# lednode2.net
KiCad netlist of a schematic drawn in EAGLE
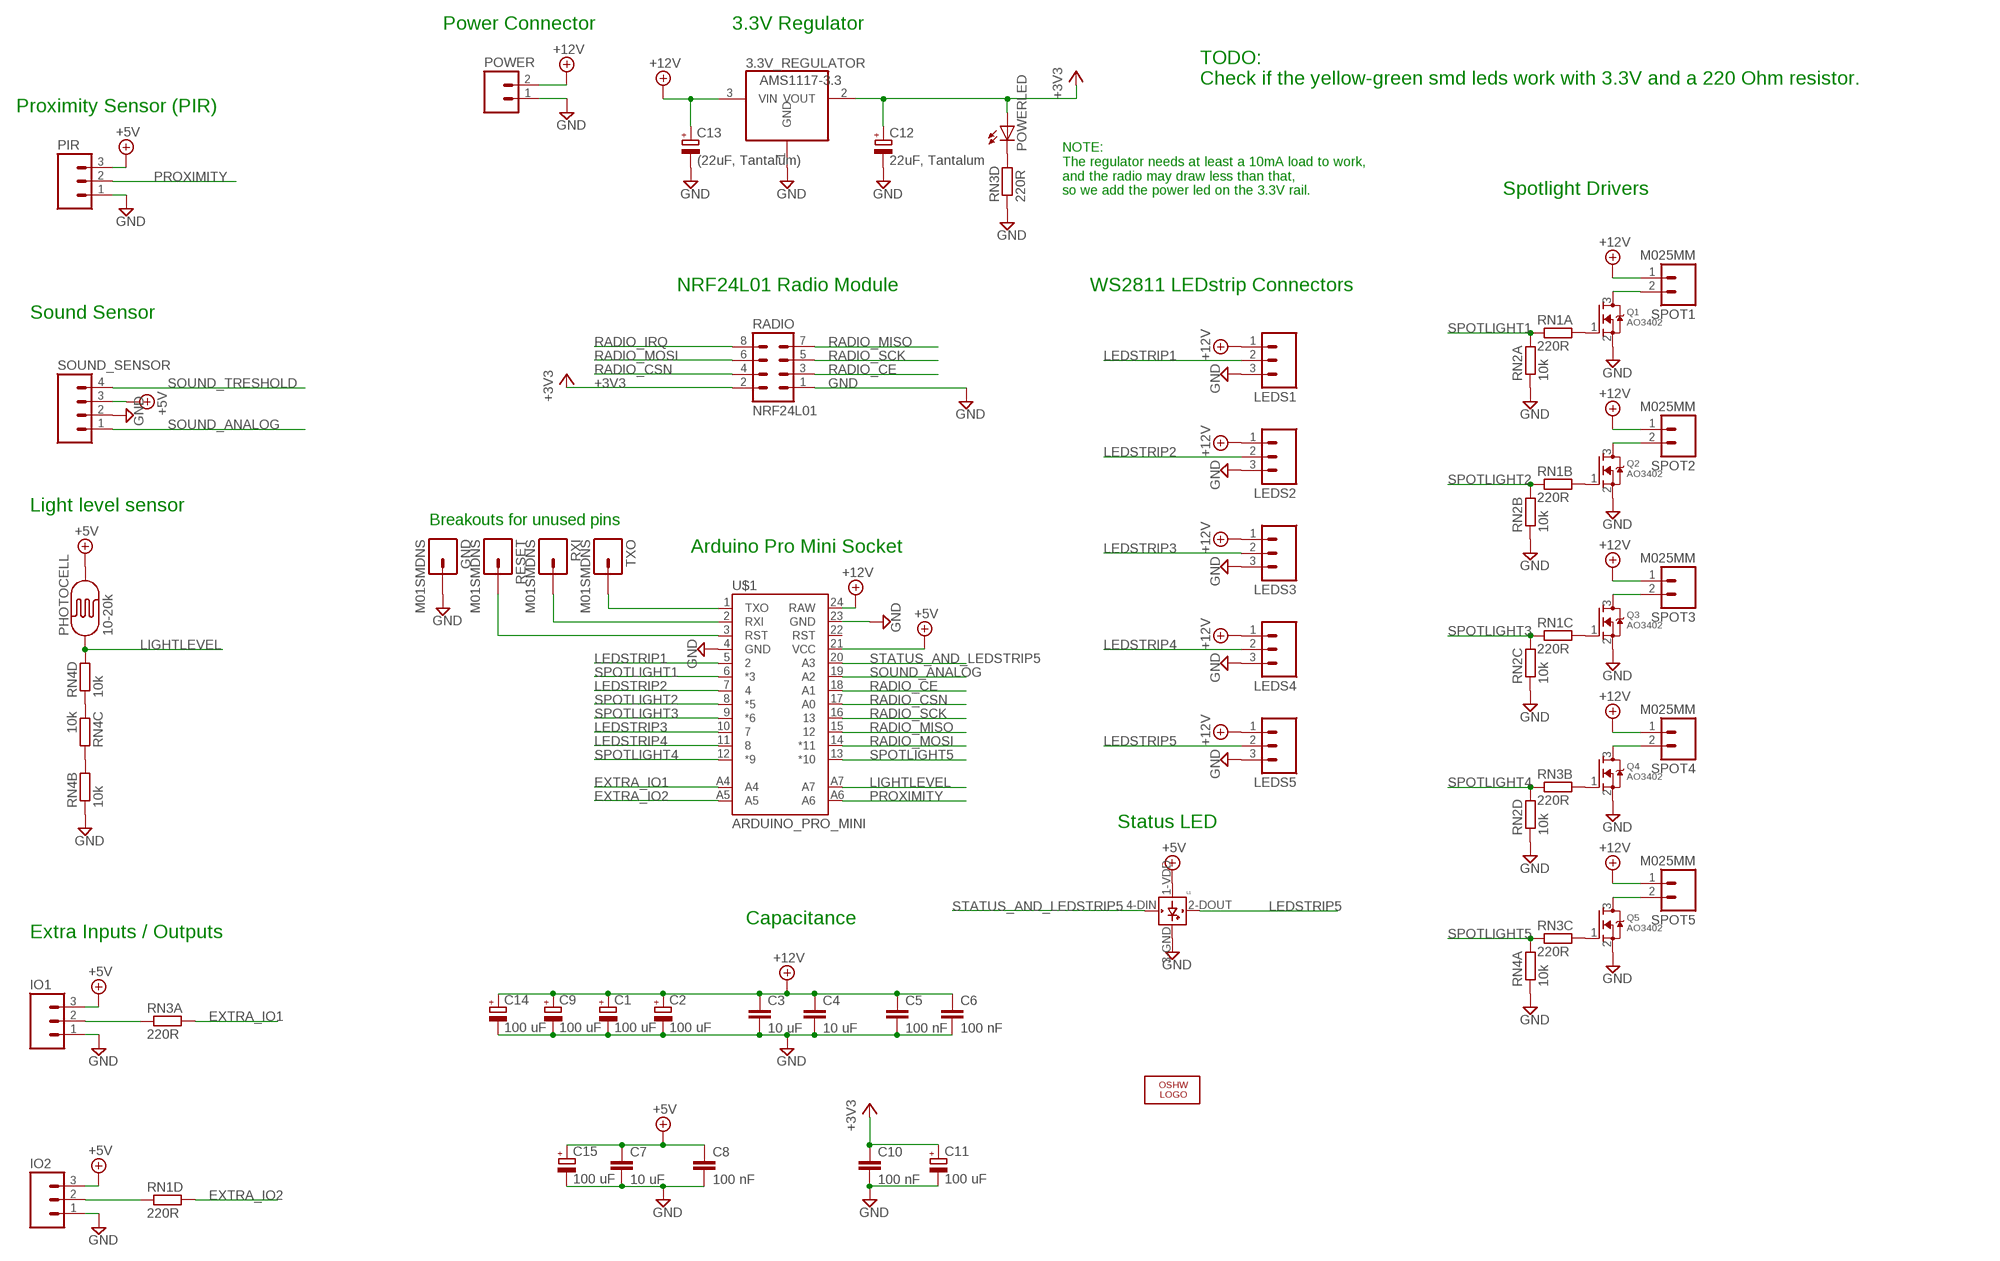
[diagram p0: schematic, sheet 1]

(export (version "E")
  (design (tool "Eeschema 10.0.6"))
  (components
    (comp (ref "3.3V_REGULATOR")
      (value "AMS1117-3.3")
      (footprint "eagle-import:SOT223")
      (fields (field (name "MPN") "REG1117"))
      (libsource (lib "eagle-import") (part "REG1117"))
    )
    (comp (ref "C1")
      (value "100 uF")
      (footprint "eagle-import:E2,5-6")
      (libsource (lib "eagle-import") (part "CPOL-EUE2.5-6"))
    )
    (comp (ref "C2")
      (value "100 uF")
      (footprint "eagle-import:E2,5-6")
      (libsource (lib "eagle-import") (part "CPOL-EUE2.5-6"))
    )
    (comp (ref "C3")
      (value "10 uF")
      (footprint "eagle-import:C1206")
      (libsource (lib "eagle-import") (part "C-EUC1206"))
    )
    (comp (ref "C4")
      (value "10 uF")
      (footprint "eagle-import:C1206")
      (libsource (lib "eagle-import") (part "C-EUC1206"))
    )
    (comp (ref "C5")
      (value "100 nF")
      (footprint "eagle-import:C0805")
      (libsource (lib "eagle-import") (part "C-EUC0805"))
    )
    (comp (ref "C6")
      (value "100 nF")
      (footprint "eagle-import:C0805")
      (libsource (lib "eagle-import") (part "C-EUC0805"))
    )
    (comp (ref "C7")
      (value "10 uF")
      (footprint "eagle-import:C1206")
      (libsource (lib "eagle-import") (part "C-EUC1206"))
    )
    (comp (ref "C8")
      (value "100 nF")
      (footprint "eagle-import:C0805")
      (libsource (lib "eagle-import") (part "C-EUC0805"))
    )
    (comp (ref "C9")
      (value "100 uF")
      (footprint "eagle-import:E2,5-6")
      (libsource (lib "eagle-import") (part "CPOL-EUE2.5-6"))
    )
    (comp (ref "C10")
      (value "100 nF")
      (footprint "eagle-import:C0805")
      (libsource (lib "eagle-import") (part "C-EUC0805"))
    )
    (comp (ref "C11")
      (value "100 uF")
      (footprint "eagle-import:E2,5-6")
      (libsource (lib "eagle-import") (part "CPOL-EUE2.5-6"))
    )
    (comp (ref "C12")
      (value "22uF, Tantalum")
      (footprint "eagle-import:SMC_A")
      (libsource (lib "eagle-import") (part "CPOL-EUSMCA"))
    )
    (comp (ref "C13")
      (value "(22uF, Tantalum)")
      (footprint "eagle-import:SMC_A")
      (libsource (lib "eagle-import") (part "CPOL-EUSMCA"))
    )
    (comp (ref "C14")
      (value "100 uF")
      (footprint "eagle-import:E2,5-6")
      (libsource (lib "eagle-import") (part "CPOL-EUE2.5-6"))
    )
    (comp (ref "C15")
      (value "100 uF")
      (footprint "eagle-import:E2,5-6")
      (libsource (lib "eagle-import") (part "CPOL-EUE2.5-6"))
    )
    (comp (ref "GND")
      (value "M01SMDNS")
      (footprint "eagle-import:1X01NS")
      (libsource (lib "eagle-import") (part "M01SMDNS"))
    )
    (comp (ref "IO1")
      (value "M03PTH")
      (footprint "eagle-import:1X03")
      (libsource (lib "eagle-import") (part "M03PTH"))
    )
    (comp (ref "IO2")
      (value "M03PTH")
      (footprint "eagle-import:1X03")
      (libsource (lib "eagle-import") (part "M03PTH"))
    )
    (comp (ref "L1")
      (value "WS2812B")
      (footprint "eagle-import:WS2812B")
      (libsource (lib "eagle-import") (part "WS2812B"))
    )
    (comp (ref "LEDS1")
      (value "M03LONGPADS")
      (footprint "eagle-import:1X03_LONGPADS")
      (libsource (lib "eagle-import") (part "M03LONGPADS"))
    )
    (comp (ref "LEDS2")
      (value "M03LONGPADS")
      (footprint "eagle-import:1X03_LONGPADS")
      (libsource (lib "eagle-import") (part "M03LONGPADS"))
    )
    (comp (ref "LEDS3")
      (value "M03LONGPADS")
      (footprint "eagle-import:1X03_LONGPADS")
      (libsource (lib "eagle-import") (part "M03LONGPADS"))
    )
    (comp (ref "LEDS4")
      (value "M03LONGPADS")
      (footprint "eagle-import:1X03_LONGPADS")
      (libsource (lib "eagle-import") (part "M03LONGPADS"))
    )
    (comp (ref "LEDS5")
      (value "M03LONGPADS")
      (footprint "eagle-import:1X03_LONGPADS")
      (libsource (lib "eagle-import") (part "M03LONGPADS"))
    )
    (comp (ref "LOGO3")
      (value "LOGO-OSHW-8MILX0100-NT")
      (footprint "eagle-import:OSHW_8X100_NOTEXT")
      (libsource (lib "eagle-import") (part "LOGO-OSHW-8MILX0100-NT"))
    )
    (comp (ref "PHOTOCELL")
      (value "10-20k")
      (footprint "eagle-import:PHOTOCELL")
      (libsource (lib "eagle-import") (part "PHOTOCELLPTH"))
    )
    (comp (ref "PIR")
      (value "M03PTH")
      (footprint "eagle-import:1X03")
      (libsource (lib "eagle-import") (part "M03PTH"))
    )
    (comp (ref "POWER")
      (value "M025MM")
      (footprint "eagle-import:SCREWTERMINAL-5MM-2")
      (libsource (lib "eagle-import") (part "M025MM"))
    )
    (comp (ref "POWERLED")
      (value "LEDSMT1206")
      (footprint "eagle-import:1206")
      (libsource (lib "eagle-import") (part "LEDSMT1206"))
    )
    (comp (ref "Q1")
      (value "AO3402")
      (footprint "eagle-import:SOT23-W")
      (libsource (lib "eagle-import") (part "MOSFET-NWAVE"))
    )
    (comp (ref "Q2")
      (value "AO3402")
      (footprint "eagle-import:SOT23-W")
      (libsource (lib "eagle-import") (part "MOSFET-NWAVE"))
    )
    (comp (ref "Q3")
      (value "AO3402")
      (footprint "eagle-import:SOT23-W")
      (libsource (lib "eagle-import") (part "MOSFET-NWAVE"))
    )
    (comp (ref "Q4")
      (value "AO3402")
      (footprint "eagle-import:SOT23-W")
      (libsource (lib "eagle-import") (part "MOSFET-NWAVE"))
    )
    (comp (ref "Q5")
      (value "AO3402")
      (footprint "eagle-import:SOT23-W")
      (libsource (lib "eagle-import") (part "MOSFET-NWAVE"))
    )
    (comp (ref "RADIO")
      (value "NRF24L01")
      (footprint "eagle-import:MA04-2")
      (libsource (lib "eagle-import") (part "MA04-2"))
    )
    (comp (ref "RESET")
      (value "M01SMDNS")
      (footprint "eagle-import:1X01NS")
      (libsource (lib "eagle-import") (part "M01SMDNS"))
    )
    (comp (ref "RN1")
      (value "220R")
      (footprint "eagle-import:RN8P-4R-CRA06S")
      (libsource (lib "eagle-import") (part "RESISTOR_ARRAY_4"))
    )
    (comp (ref "RN2")
      (value "10k")
      (footprint "eagle-import:RN8P-4R-CRA06S")
      (libsource (lib "eagle-import") (part "RESISTOR_ARRAY_4"))
    )
    (comp (ref "RN3")
      (value "220R")
      (footprint "eagle-import:RN8P-4R-CRA06S")
      (libsource (lib "eagle-import") (part "RESISTOR_ARRAY_4"))
    )
    (comp (ref "RN4")
      (value "10k")
      (footprint "eagle-import:RN8P-4R-CRA06S")
      (libsource (lib "eagle-import") (part "RESISTOR_ARRAY_4"))
    )
    (comp (ref "RXI")
      (value "M01SMDNS")
      (footprint "eagle-import:1X01NS")
      (libsource (lib "eagle-import") (part "M01SMDNS"))
    )
    (comp (ref "SOUND_SENSOR")
      (value "M041X04_NO_SILK")
      (footprint "eagle-import:1X04_NO_SILK")
      (libsource (lib "eagle-import") (part "M041X04_NO_SILK"))
    )
    (comp (ref "SPOT1")
      (value "M025MM")
      (footprint "eagle-import:SCREWTERMINAL-5MM-2")
      (libsource (lib "eagle-import") (part "SparkFun-Connectors_M025MM"))
    )
    (comp (ref "SPOT2")
      (value "M025MM")
      (footprint "eagle-import:SCREWTERMINAL-5MM-2")
      (libsource (lib "eagle-import") (part "SparkFun-Connectors_M025MM"))
    )
    (comp (ref "SPOT3")
      (value "M025MM")
      (footprint "eagle-import:SCREWTERMINAL-5MM-2")
      (libsource (lib "eagle-import") (part "SparkFun-Connectors_M025MM"))
    )
    (comp (ref "SPOT4")
      (value "M025MM")
      (footprint "eagle-import:SCREWTERMINAL-5MM-2")
      (libsource (lib "eagle-import") (part "SparkFun-Connectors_M025MM"))
    )
    (comp (ref "SPOT5")
      (value "M025MM")
      (footprint "eagle-import:SCREWTERMINAL-5MM-2")
      (libsource (lib "eagle-import") (part "SparkFun-Connectors_M025MM"))
    )
    (comp (ref "TXO")
      (value "M01SMDNS")
      (footprint "eagle-import:1X01NS")
      (libsource (lib "eagle-import") (part "M01SMDNS"))
    )
    (comp (ref "U$1")
      (value "ARDUINO_PRO_MINI")
      (footprint "eagle-import:ARDUINO_PRO_MINI")
      (libsource (lib "eagle-import") (part "ARDUINO_PRO_MINI"))
    )
  )
  (nets
    (net (code "1") (name "+3V3") (class "Default")
      (node (ref "3.3V_REGULATOR") (pin "2") (pinfunction "VOUT_2") (pintype "output"))
      (node (ref "C10") (pin "1") (pinfunction "1_1") (pintype "passive"))
      (node (ref "C11") (pin "+") (pinfunction "+_+") (pintype "passive"))
      (node (ref "C12") (pin "+") (pinfunction "+_+") (pintype "passive"))
      (node (ref "POWERLED") (pin "A") (pinfunction "A_A") (pintype "passive"))
      (node (ref "RADIO") (pin "2") (pinfunction "2_2") (pintype "passive"))
    )
    (net (code "2") (name "+5V") (class "Default")
      (node (ref "C15") (pin "+") (pinfunction "+_+") (pintype "passive"))
      (node (ref "C7") (pin "1") (pinfunction "1_1") (pintype "passive"))
      (node (ref "C8") (pin "1") (pinfunction "1_1") (pintype "passive"))
      (node (ref "IO1") (pin "3") (pinfunction "3_3") (pintype "passive"))
      (node (ref "IO2") (pin "3") (pinfunction "3_3") (pintype "passive"))
      (node (ref "L1") (pin "1-VDD") (pinfunction "VDD_1-VDD") (pintype "bidirectional"))
      (node (ref "PHOTOCELL") (pin "2") (pinfunction "P$2_2") (pintype "bidirectional"))
      (node (ref "PIR") (pin "3") (pinfunction "3_3") (pintype "passive"))
      (node (ref "SOUND_SENSOR") (pin "3") (pinfunction "3_3") (pintype "passive"))
      (node (ref "U$1") (pin "21") (pinfunction "VCC_21") (pintype "bidirectional"))
    )
    (net (code "3") (name "+12V") (class "Default")
      (node (ref "3.3V_REGULATOR") (pin "3") (pinfunction "VIN_3") (pintype "input"))
      (node (ref "C1") (pin "+") (pinfunction "+_+") (pintype "passive"))
      (node (ref "C13") (pin "+") (pinfunction "+_+") (pintype "passive"))
      (node (ref "C14") (pin "+") (pinfunction "+_+") (pintype "passive"))
      (node (ref "C2") (pin "+") (pinfunction "+_+") (pintype "passive"))
      (node (ref "C3") (pin "1") (pinfunction "1_1") (pintype "passive"))
      (node (ref "C4") (pin "1") (pinfunction "1_1") (pintype "passive"))
      (node (ref "C5") (pin "1") (pinfunction "1_1") (pintype "passive"))
      (node (ref "C6") (pin "1") (pinfunction "1_1") (pintype "passive"))
      (node (ref "C9") (pin "+") (pinfunction "+_+") (pintype "passive"))
      (node (ref "LEDS1") (pin "1") (pinfunction "1_1") (pintype "passive"))
      (node (ref "LEDS2") (pin "1") (pinfunction "1_1") (pintype "passive"))
      (node (ref "LEDS3") (pin "1") (pinfunction "1_1") (pintype "passive"))
      (node (ref "LEDS4") (pin "1") (pinfunction "1_1") (pintype "passive"))
      (node (ref "LEDS5") (pin "1") (pinfunction "1_1") (pintype "passive"))
      (node (ref "POWER") (pin "2") (pinfunction "2_2") (pintype "passive"))
      (node (ref "SPOT1") (pin "1") (pinfunction "1_1") (pintype "passive"))
      (node (ref "SPOT2") (pin "1") (pinfunction "1_1") (pintype "passive"))
      (node (ref "SPOT3") (pin "1") (pinfunction "1_1") (pintype "passive"))
      (node (ref "SPOT4") (pin "1") (pinfunction "1_1") (pintype "passive"))
      (node (ref "SPOT5") (pin "1") (pinfunction "1_1") (pintype "passive"))
      (node (ref "U$1") (pin "24") (pinfunction "RAW_24") (pintype "bidirectional"))
    )
    (net (code "4") (name "/EXTRA_IO1") (class "Default")
      (node (ref "RN3") (pin "8") (pinfunction "2_8") (pintype "passive"))
      (node (ref "U$1") (pin "A4") (pinfunction "A4_A4") (pintype "bidirectional"))
    )
    (net (code "5") (name "/EXTRA_IO2") (class "Default")
      (node (ref "RN1") (pin "5") (pinfunction "2_5") (pintype "passive"))
      (node (ref "U$1") (pin "A5") (pinfunction "A5_A5") (pintype "bidirectional"))
    )
    (net (code "6") (name "/LEDSTRIP1") (class "Default")
      (node (ref "LEDS1") (pin "2") (pinfunction "2_2") (pintype "passive"))
      (node (ref "U$1") (pin "5") (pinfunction "2_5") (pintype "bidirectional"))
    )
    (net (code "7") (name "/LEDSTRIP2") (class "Default")
      (node (ref "LEDS2") (pin "2") (pinfunction "2_2") (pintype "passive"))
      (node (ref "U$1") (pin "7") (pinfunction "4_7") (pintype "bidirectional"))
    )
    (net (code "8") (name "/LEDSTRIP3") (class "Default")
      (node (ref "LEDS3") (pin "2") (pinfunction "2_2") (pintype "passive"))
      (node (ref "U$1") (pin "10") (pinfunction "7_10") (pintype "bidirectional"))
    )
    (net (code "9") (name "/LEDSTRIP4") (class "Default")
      (node (ref "LEDS4") (pin "2") (pinfunction "2_2") (pintype "passive"))
      (node (ref "U$1") (pin "11") (pinfunction "8_11") (pintype "bidirectional"))
    )
    (net (code "10") (name "/LEDSTRIP5") (class "Default")
      (node (ref "L1") (pin "2-DOUT") (pinfunction "DOUT_2-DOUT") (pintype "output"))
      (node (ref "LEDS5") (pin "2") (pinfunction "2_2") (pintype "passive"))
    )
    (net (code "11") (name "/LIGHTLEVEL") (class "Default")
      (node (ref "PHOTOCELL") (pin "1") (pinfunction "P$1_1") (pintype "bidirectional"))
      (node (ref "RN4") (pin "5") (pinfunction "2_5") (pintype "passive"))
      (node (ref "U$1") (pin "A7") (pinfunction "A7_A7") (pintype "bidirectional"))
    )
    (net (code "12") (name "/PROXIMITY") (class "Default")
      (node (ref "PIR") (pin "2") (pinfunction "2_2") (pintype "passive"))
      (node (ref "U$1") (pin "A6") (pinfunction "A6_A6") (pintype "bidirectional"))
    )
    (net (code "13") (name "/RADIO_CE") (class "Default")
      (node (ref "RADIO") (pin "3") (pinfunction "3_3") (pintype "passive"))
      (node (ref "U$1") (pin "18") (pinfunction "A1_18") (pintype "bidirectional"))
    )
    (net (code "14") (name "/RADIO_CSN") (class "Default")
      (node (ref "RADIO") (pin "4") (pinfunction "4_4") (pintype "passive"))
      (node (ref "U$1") (pin "17") (pinfunction "A0_17") (pintype "bidirectional"))
    )
    (net (code "15") (name "/RADIO_IRQ") (class "Default")
      (node (ref "RADIO") (pin "8") (pinfunction "8_8") (pintype "passive"))
    )
    (net (code "16") (name "/RADIO_MISO") (class "Default")
      (node (ref "RADIO") (pin "7") (pinfunction "7_7") (pintype "passive"))
      (node (ref "U$1") (pin "15") (pinfunction "12_15") (pintype "bidirectional"))
    )
    (net (code "17") (name "/RADIO_MOSI") (class "Default")
      (node (ref "RADIO") (pin "6") (pinfunction "6_6") (pintype "passive"))
      (node (ref "U$1") (pin "14") (pinfunction "*11_14") (pintype "bidirectional"))
    )
    (net (code "18") (name "/RADIO_SCK") (class "Default")
      (node (ref "RADIO") (pin "5") (pinfunction "5_5") (pintype "passive"))
      (node (ref "U$1") (pin "16") (pinfunction "13_16") (pintype "bidirectional"))
    )
    (net (code "19") (name "/SOUND_ANALOG") (class "Default")
      (node (ref "SOUND_SENSOR") (pin "1") (pinfunction "1_1") (pintype "passive"))
      (node (ref "U$1") (pin "19") (pinfunction "A2_19") (pintype "bidirectional"))
    )
    (net (code "20") (name "/SOUND_TRESHOLD") (class "Default")
      (node (ref "SOUND_SENSOR") (pin "4") (pinfunction "4_4") (pintype "passive"))
    )
    (net (code "21") (name "/SPOTLIGHT1") (class "Default")
      (node (ref "RN1") (pin "1") (pinfunction "1_1") (pintype "passive"))
      (node (ref "RN2") (pin "8") (pinfunction "2_8") (pintype "passive"))
      (node (ref "U$1") (pin "6") (pinfunction "*3_6") (pintype "bidirectional"))
    )
    (net (code "22") (name "/SPOTLIGHT2") (class "Default")
      (node (ref "RN1") (pin "2") (pinfunction "1_2") (pintype "passive"))
      (node (ref "RN2") (pin "7") (pinfunction "2_7") (pintype "passive"))
      (node (ref "U$1") (pin "8") (pinfunction "*5_8") (pintype "bidirectional"))
    )
    (net (code "23") (name "/SPOTLIGHT3") (class "Default")
      (node (ref "RN1") (pin "3") (pinfunction "1_3") (pintype "passive"))
      (node (ref "RN2") (pin "6") (pinfunction "2_6") (pintype "passive"))
      (node (ref "U$1") (pin "9") (pinfunction "*6_9") (pintype "bidirectional"))
    )
    (net (code "24") (name "/SPOTLIGHT4") (class "Default")
      (node (ref "RN2") (pin "5") (pinfunction "2_5") (pintype "passive"))
      (node (ref "RN3") (pin "2") (pinfunction "1_2") (pintype "passive"))
      (node (ref "U$1") (pin "12") (pinfunction "*9_12") (pintype "bidirectional"))
    )
    (net (code "25") (name "/SPOTLIGHT5") (class "Default")
      (node (ref "RN3") (pin "3") (pinfunction "1_3") (pintype "passive"))
      (node (ref "RN4") (pin "8") (pinfunction "2_8") (pintype "passive"))
      (node (ref "U$1") (pin "13") (pinfunction "*10_13") (pintype "bidirectional"))
    )
    (net (code "26") (name "/STATUS_AND_LEDSTRIP5") (class "Default")
      (node (ref "L1") (pin "4-DIN") (pinfunction "DIN_4-DIN") (pintype "input"))
      (node (ref "U$1") (pin "20") (pinfunction "A3_20") (pintype "bidirectional"))
    )
    (net (code "27") (name "GND") (class "Default")
      (node (ref "3.3V_REGULATOR") (pin "1") (pinfunction "GND_1") (pintype "power_in"))
      (node (ref "C1") (pin "-") (pinfunction "-_-") (pintype "passive"))
      (node (ref "C10") (pin "2") (pinfunction "2_2") (pintype "passive"))
      (node (ref "C11") (pin "-") (pinfunction "-_-") (pintype "passive"))
      (node (ref "C12") (pin "-") (pinfunction "-_-") (pintype "passive"))
      (node (ref "C13") (pin "-") (pinfunction "-_-") (pintype "passive"))
      (node (ref "C14") (pin "-") (pinfunction "-_-") (pintype "passive"))
      (node (ref "C15") (pin "-") (pinfunction "-_-") (pintype "passive"))
      (node (ref "C2") (pin "-") (pinfunction "-_-") (pintype "passive"))
      (node (ref "C3") (pin "2") (pinfunction "2_2") (pintype "passive"))
      (node (ref "C4") (pin "2") (pinfunction "2_2") (pintype "passive"))
      (node (ref "C5") (pin "2") (pinfunction "2_2") (pintype "passive"))
      (node (ref "C6") (pin "2") (pinfunction "2_2") (pintype "passive"))
      (node (ref "C7") (pin "2") (pinfunction "2_2") (pintype "passive"))
      (node (ref "C8") (pin "2") (pinfunction "2_2") (pintype "passive"))
      (node (ref "C9") (pin "-") (pinfunction "-_-") (pintype "passive"))
      (node (ref "GND") (pin "1") (pinfunction "1_1") (pintype "passive"))
      (node (ref "IO1") (pin "1") (pinfunction "1_1") (pintype "passive"))
      (node (ref "IO2") (pin "1") (pinfunction "1_1") (pintype "passive"))
      (node (ref "L1") (pin "3-GND") (pinfunction "GND_3-GND") (pintype "bidirectional"))
      (node (ref "LEDS1") (pin "3") (pinfunction "3_3") (pintype "passive"))
      (node (ref "LEDS2") (pin "3") (pinfunction "3_3") (pintype "passive"))
      (node (ref "LEDS3") (pin "3") (pinfunction "3_3") (pintype "passive"))
      (node (ref "LEDS4") (pin "3") (pinfunction "3_3") (pintype "passive"))
      (node (ref "LEDS5") (pin "3") (pinfunction "3_3") (pintype "passive"))
      (node (ref "PIR") (pin "1") (pinfunction "1_1") (pintype "passive"))
      (node (ref "POWER") (pin "1") (pinfunction "1_1") (pintype "passive"))
      (node (ref "Q1") (pin "2") (pinfunction "S_2") (pintype "bidirectional"))
      (node (ref "Q2") (pin "2") (pinfunction "S_2") (pintype "bidirectional"))
      (node (ref "Q3") (pin "2") (pinfunction "S_2") (pintype "bidirectional"))
      (node (ref "Q4") (pin "2") (pinfunction "S_2") (pintype "bidirectional"))
      (node (ref "Q5") (pin "2") (pinfunction "S_2") (pintype "bidirectional"))
      (node (ref "RADIO") (pin "1") (pinfunction "1_1") (pintype "passive"))
      (node (ref "RN2") (pin "1") (pinfunction "1_1") (pintype "passive"))
      (node (ref "RN2") (pin "2") (pinfunction "1_2") (pintype "passive"))
      (node (ref "RN2") (pin "3") (pinfunction "1_3") (pintype "passive"))
      (node (ref "RN2") (pin "4") (pinfunction "1_4") (pintype "passive"))
      (node (ref "RN3") (pin "4") (pinfunction "1_4") (pintype "passive"))
      (node (ref "RN4") (pin "1") (pinfunction "1_1") (pintype "passive"))
      (node (ref "RN4") (pin "2") (pinfunction "1_2") (pintype "passive"))
      (node (ref "SOUND_SENSOR") (pin "2") (pinfunction "2_2") (pintype "passive"))
      (node (ref "U$1") (pin "23") (pinfunction "GND_23") (pintype "bidirectional"))
      (node (ref "U$1") (pin "4") (pinfunction "GND_4") (pintype "bidirectional"))
    )
    (net (code "28") (name "Net-(IO1-Pad2)") (class "Default")
      (node (ref "IO1") (pin "2") (pinfunction "2_2") (pintype "passive"))
      (node (ref "RN3") (pin "1") (pinfunction "1_1") (pintype "passive"))
    )
    (net (code "29") (name "Net-(Q1-D)") (class "Default")
      (node (ref "Q1") (pin "3") (pinfunction "D_3") (pintype "bidirectional"))
      (node (ref "SPOT1") (pin "2") (pinfunction "2_2") (pintype "passive"))
    )
    (net (code "30") (name "Net-(Q1-G)") (class "Default")
      (node (ref "Q1") (pin "1") (pinfunction "G_1") (pintype "bidirectional"))
      (node (ref "RN1") (pin "8") (pinfunction "2_8") (pintype "passive"))
    )
    (net (code "31") (name "Net-(Q2-D)") (class "Default")
      (node (ref "Q2") (pin "3") (pinfunction "D_3") (pintype "bidirectional"))
      (node (ref "SPOT2") (pin "2") (pinfunction "2_2") (pintype "passive"))
    )
    (net (code "32") (name "Net-(Q2-G)") (class "Default")
      (node (ref "Q2") (pin "1") (pinfunction "G_1") (pintype "bidirectional"))
      (node (ref "RN1") (pin "7") (pinfunction "2_7") (pintype "passive"))
    )
    (net (code "33") (name "Net-(Q3-D)") (class "Default")
      (node (ref "Q3") (pin "3") (pinfunction "D_3") (pintype "bidirectional"))
      (node (ref "SPOT3") (pin "2") (pinfunction "2_2") (pintype "passive"))
    )
    (net (code "34") (name "Net-(Q3-G)") (class "Default")
      (node (ref "Q3") (pin "1") (pinfunction "G_1") (pintype "bidirectional"))
      (node (ref "RN1") (pin "6") (pinfunction "2_6") (pintype "passive"))
    )
    (net (code "35") (name "Net-(Q4-D)") (class "Default")
      (node (ref "Q4") (pin "3") (pinfunction "D_3") (pintype "bidirectional"))
      (node (ref "SPOT4") (pin "2") (pinfunction "2_2") (pintype "passive"))
    )
    (net (code "36") (name "Net-(Q4-G)") (class "Default")
      (node (ref "Q4") (pin "1") (pinfunction "G_1") (pintype "bidirectional"))
      (node (ref "RN3") (pin "7") (pinfunction "2_7") (pintype "passive"))
    )
    (net (code "37") (name "Net-(Q5-D)") (class "Default")
      (node (ref "Q5") (pin "3") (pinfunction "D_3") (pintype "bidirectional"))
      (node (ref "SPOT5") (pin "2") (pinfunction "2_2") (pintype "passive"))
    )
    (net (code "38") (name "Net-(Q5-G)") (class "Default")
      (node (ref "Q5") (pin "1") (pinfunction "G_1") (pintype "bidirectional"))
      (node (ref "RN3") (pin "6") (pinfunction "2_6") (pintype "passive"))
    )
    (net (code "39") (name "Net-(RESET-Pad1)") (class "Default")
      (node (ref "RESET") (pin "1") (pinfunction "1_1") (pintype "passive"))
      (node (ref "U$1") (pin "3") (pinfunction "RST_3") (pintype "bidirectional"))
    )
    (net (code "40") (name "Net-(RN1D-1)") (class "Default")
      (node (ref "IO2") (pin "2") (pinfunction "2_2") (pintype "passive"))
      (node (ref "RN1") (pin "4") (pinfunction "1_4") (pintype "passive"))
    )
    (net (code "41") (name "Net-(RN3D-2)") (class "Default")
      (node (ref "POWERLED") (pin "C") (pinfunction "C_C") (pintype "passive"))
      (node (ref "RN3") (pin "5") (pinfunction "2_5") (pintype "passive"))
    )
    (net (code "42") (name "Net-(RN4B-2)") (class "Default")
      (node (ref "RN4") (pin "6") (pinfunction "2_6") (pintype "passive"))
      (node (ref "RN4") (pin "7") (pinfunction "2_7") (pintype "passive"))
    )
    (net (code "43") (name "Net-(RN4C-1)") (class "Default")
      (node (ref "RN4") (pin "3") (pinfunction "1_3") (pintype "passive"))
      (node (ref "RN4") (pin "4") (pinfunction "1_4") (pintype "passive"))
    )
    (net (code "44") (name "Net-(U$1-RXI)") (class "Default")
      (node (ref "RXI") (pin "1") (pinfunction "1_1") (pintype "passive"))
      (node (ref "U$1") (pin "2") (pinfunction "RXI_2") (pintype "bidirectional"))
    )
    (net (code "45") (name "Net-(U$1-TXO)") (class "Default")
      (node (ref "TXO") (pin "1") (pinfunction "1_1") (pintype "passive"))
      (node (ref "U$1") (pin "1") (pinfunction "TXO_1") (pintype "bidirectional"))
    )
    (net (code "46") (name "unconnected-(U$1-RST-Pad22)") (class "Default")
      (node (ref "U$1") (pin "22") (pinfunction "RST_22") (pintype "bidirectional"))
    )
  )
)
